# SCH_SOURCE.net
KiCad netlist of a schematic drawn in Altium Designer
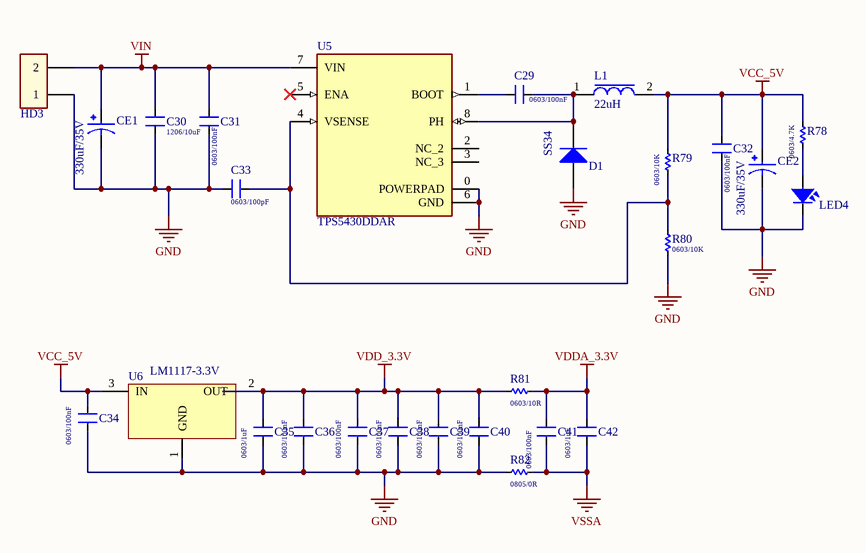
[diagram p0: SCH_SOURCE.SchDoc]

(export (version "E")
  (design (tool "Eeschema 10.0.6"))
  (components
    (comp (ref "C29")
      (value "0603/100nF")
      (footprint "CAP-SMD-0603")
      (libsource (lib "RAL") (part "CAP-SMD"))
    )
    (comp (ref "C30") (value "1206/10uF") (footprint "CAP-SMD-1206") (libsource (lib "RAL") (part "CAP-SMD")))
    (comp (ref "C31")
      (value "0603/100nF")
      (footprint "CAP-SMD-0603")
      (libsource (lib "RAL") (part "CAP-SMD"))
    )
    (comp (ref "C32")
      (value "0603/100nF")
      (footprint "CAP-SMD-0603")
      (libsource (lib "RAL") (part "CAP-SMD"))
    )
    (comp (ref "C33")
      (value "0603/100pF")
      (footprint "CAP-SMD-0603")
      (libsource (lib "RAL") (part "CAP-SMD"))
    )
    (comp (ref "C34")
      (value "0603/100nF")
      (footprint "CAP-SMD-0603")
      (libsource (lib "RAL") (part "CAP-SMD"))
    )
    (comp (ref "C35") (value "0603/1uF") (footprint "CAP-SMD-0603") (libsource (lib "RAL") (part "CAP-SMD")))
    (comp (ref "C36")
      (value "0603/100nF")
      (footprint "CAP-SMD-0603")
      (libsource (lib "RAL") (part "CAP-SMD"))
    )
    (comp (ref "C37")
      (value "0603/100nF")
      (footprint "CAP-SMD-0603")
      (libsource (lib "RAL") (part "CAP-SMD"))
    )
    (comp (ref "C38")
      (value "0603/100nF")
      (footprint "CAP-SMD-0603")
      (libsource (lib "RAL") (part "CAP-SMD"))
    )
    (comp (ref "C39")
      (value "0603/100nF")
      (footprint "CAP-SMD-0603")
      (libsource (lib "RAL") (part "CAP-SMD"))
    )
    (comp (ref "C40")
      (value "0603/100nF")
      (footprint "CAP-SMD-0603")
      (libsource (lib "RAL") (part "CAP-SMD"))
    )
    (comp (ref "C41")
      (value "0603/100nF")
      (footprint "CAP-SMD-0603")
      (libsource (lib "RAL") (part "CAP-SMD"))
    )
    (comp (ref "C42") (value "0603/1uF") (footprint "CAP-SMD-0603") (libsource (lib "RAL") (part "CAP-SMD")))
    (comp (ref "CE1")
      (value "330uF/35V")
      (footprint "CAP-DIP-8x16mm")
      (description "00077126")
      (fields (field (name "PUBLISHER") "Altium Limited"))
      (libsource (lib "mySche") (part "CAP-ALU-DIP"))
    )
    (comp (ref "CE2")
      (value "330uF/35V")
      (footprint "CAP-DIP-8x16mm")
      (description "00077126")
      (fields (field (name "PUBLISHER") "Altium Limited"))
      (libsource (lib "mySche") (part "CAP-ALU-DIP"))
    )
    (comp (ref "D1")
      (value "SS34")
      (footprint "SMB")
      (description "Default Diode")
      (fields (field (name "PUBLISHER") "Altium Limited"))
      (libsource (lib "RAL") (part "Diode SMD"))
    )
    (comp (ref "HD3") (value "Header2") (footprint "XH2.54M-2") (libsource (lib "lib") (part "Header2")))
    (comp (ref "L1")
      (value "22uH")
      (footprint "L-SMD-M-7.3x4.5")
      (fields
        (field (name "PARTNO") "78477010")
        (field (name "MANUFACTURER") "Wurth Elektronik")
        (field (name "CREATED BY") "Baojun Chen")
      )
      (libsource (lib "RAL") (part "L-SMD-1"))
    )
    (comp (ref "LED4") (value "LED") (footprint "LED-0805-Green") (libsource (lib "RAL") (part "LED1-SMD")))
    (comp (ref "R78")
      (value "0603/4.7K")
      (footprint "RES-SMD-0603")
      (description "Resistor")
      (fields
        (field (name "MANUFACTURER") "Generic Components")
        (field (name "PUBLISHER") "Altium Hobart Technology Centre")
      )
      (libsource (lib "RAL") (part "Res-SMD"))
    )
    (comp (ref "R79")
      (value "0603/10K")
      (footprint "RES-SMD-0603")
      (description "Resistor")
      (fields
        (field (name "MANUFACTURER") "Generic Components")
        (field (name "PUBLISHER") "Altium Hobart Technology Centre")
      )
      (libsource (lib "RAL") (part "Res-SMD"))
    )
    (comp (ref "R80")
      (value "0603/10K")
      (footprint "RES-SMD-0603")
      (description "Resistor")
      (fields
        (field (name "MANUFACTURER") "Generic Components")
        (field (name "PUBLISHER") "Altium Hobart Technology Centre")
      )
      (libsource (lib "RAL") (part "Res-SMD"))
    )
    (comp (ref "R81")
      (value "0603/10R")
      (footprint "RES-SMD-0603")
      (description "Resistor")
      (fields
        (field (name "MANUFACTURER") "Generic Components")
        (field (name "PUBLISHER") "Altium Hobart Technology Centre")
      )
      (libsource (lib "RAL") (part "Res-SMD"))
    )
    (comp (ref "R82")
      (value "0805/0R")
      (footprint "RES-SMD-0805")
      (description "Resistor")
      (fields
        (field (name "MANUFACTURER") "Generic Components")
        (field (name "PUBLISHER") "Altium Hobart Technology Centre")
      )
      (libsource (lib "RAL") (part "Res-SMD"))
    )
    (comp (ref "U5")
      (value "TPS5430DDAR")
      (footprint "SOP-8 + GND")
      (description "5.5V to 36V Input, 3A, 500kHz Step-Down Converter")
      (fields (field (name "MF") "Texas Instruments"))
      (libsource (lib "lib") (part "TPS5430DDAR"))
    )
    (comp (ref "U6")
      (value "LM1117-3.3V")
      (footprint "TO252-123")
      (description "800mA Low-Dropout Linear Regulator")
      (fields (field (name "CREATOR") "Nguyen Ba Bien"))
      (libsource (lib "RAL") (part "IC LM1117"))
    )
  )
  (nets
    (net (code "1") (name "GND") (class "Default")
      (node (ref "C30") (pin "2") (pinfunction "2_2") (pintype "passive"))
      (node (ref "C31") (pin "2") (pinfunction "2_2") (pintype "passive"))
      (node (ref "C32") (pin "2") (pinfunction "2_2") (pintype "passive"))
      (node (ref "C33") (pin "1") (pinfunction "1_1") (pintype "passive"))
      (node (ref "C34") (pin "1") (pinfunction "1_1") (pintype "passive"))
      (node (ref "C35") (pin "1") (pinfunction "1_1") (pintype "passive"))
      (node (ref "C36") (pin "1") (pinfunction "1_1") (pintype "passive"))
      (node (ref "C37") (pin "1") (pinfunction "1_1") (pintype "passive"))
      (node (ref "C38") (pin "1") (pinfunction "1_1") (pintype "passive"))
      (node (ref "C39") (pin "1") (pinfunction "1_1") (pintype "passive"))
      (node (ref "C40") (pin "1") (pinfunction "1_1") (pintype "passive"))
      (node (ref "CE1") (pin "2") (pinfunction "2_2") (pintype "passive"))
      (node (ref "CE2") (pin "2") (pinfunction "2_2") (pintype "passive"))
      (node (ref "D1") (pin "1") (pinfunction "A_1") (pintype "passive"))
      (node (ref "HD3") (pin "1") (pinfunction "1_1") (pintype "passive"))
      (node (ref "LED4") (pin "2") (pinfunction "2_2") (pintype "passive"))
      (node (ref "R80") (pin "1") (pinfunction "1_1") (pintype "passive"))
      (node (ref "R82") (pin "1") (pinfunction "1_1") (pintype "passive"))
      (node (ref "U5") (pin "0") (pinfunction "POWERPAD_0") (pintype "power_in"))
      (node (ref "U5") (pin "6") (pinfunction "GND_6") (pintype "power_in"))
      (node (ref "U6") (pin "1") (pinfunction "GND_1") (pintype "passive"))
    )
    (net (code "2") (name "Net-(D1-K)") (class "Default")
      (node (ref "C29") (pin "1") (pinfunction "1_1") (pintype "passive"))
      (node (ref "D1") (pin "2") (pinfunction "K_2") (pintype "passive"))
      (node (ref "L1") (pin "1") (pinfunction "1_1") (pintype "passive"))
      (node (ref "U5") (pin "8") (pinfunction "PH_8") (pintype "bidirectional"))
    )
    (net (code "3") (name "Net-(LED4-Pad1)") (class "Default")
      (node (ref "LED4") (pin "1") (pinfunction "1_1") (pintype "passive"))
      (node (ref "R78") (pin "2") (pinfunction "2_2") (pintype "passive"))
    )
    (net (code "4") (name "Net-(U5-BOOT)") (class "Default")
      (node (ref "C29") (pin "2") (pinfunction "2_2") (pintype "passive"))
      (node (ref "U5") (pin "1") (pinfunction "BOOT_1") (pintype "output"))
    )
    (net (code "5") (name "Net-(U5-VSENSE)") (class "Default")
      (node (ref "C33") (pin "2") (pinfunction "2_2") (pintype "passive"))
      (node (ref "R79") (pin "2") (pinfunction "2_2") (pintype "passive"))
      (node (ref "R80") (pin "2") (pinfunction "2_2") (pintype "passive"))
      (node (ref "U5") (pin "4") (pinfunction "VSENSE_4") (pintype "input"))
    )
    (net (code "6") (name "VCC_5V") (class "Default")
      (node (ref "C32") (pin "1") (pinfunction "1_1") (pintype "passive"))
      (node (ref "C34") (pin "2") (pinfunction "2_2") (pintype "passive"))
      (node (ref "CE2") (pin "1") (pinfunction "1_1") (pintype "passive"))
      (node (ref "L1") (pin "2") (pinfunction "2_2") (pintype "passive"))
      (node (ref "R78") (pin "1") (pinfunction "1_1") (pintype "passive"))
      (node (ref "R79") (pin "1") (pinfunction "1_1") (pintype "passive"))
      (node (ref "U6") (pin "3") (pinfunction "IN_3") (pintype "passive"))
    )
    (net (code "7") (name "VDDA_3.3V") (class "Default")
      (node (ref "C41") (pin "2") (pinfunction "2_2") (pintype "passive"))
      (node (ref "C42") (pin "2") (pinfunction "2_2") (pintype "passive"))
      (node (ref "R81") (pin "2") (pinfunction "2_2") (pintype "passive"))
    )
    (net (code "8") (name "VDD_3.3V") (class "Default")
      (node (ref "C35") (pin "2") (pinfunction "2_2") (pintype "passive"))
      (node (ref "C36") (pin "2") (pinfunction "2_2") (pintype "passive"))
      (node (ref "C37") (pin "2") (pinfunction "2_2") (pintype "passive"))
      (node (ref "C38") (pin "2") (pinfunction "2_2") (pintype "passive"))
      (node (ref "C39") (pin "2") (pinfunction "2_2") (pintype "passive"))
      (node (ref "C40") (pin "2") (pinfunction "2_2") (pintype "passive"))
      (node (ref "R81") (pin "1") (pinfunction "1_1") (pintype "passive"))
      (node (ref "U6") (pin "2") (pinfunction "OUT_2") (pintype "passive"))
    )
    (net (code "9") (name "VIN") (class "Default")
      (node (ref "C30") (pin "1") (pinfunction "1_1") (pintype "passive"))
      (node (ref "C31") (pin "1") (pinfunction "1_1") (pintype "passive"))
      (node (ref "CE1") (pin "1") (pinfunction "1_1") (pintype "passive"))
      (node (ref "HD3") (pin "2") (pinfunction "2_2") (pintype "passive"))
      (node (ref "U5") (pin "7") (pinfunction "VIN_7") (pintype "power_in"))
    )
    (net (code "10") (name "VSSA") (class "Default")
      (node (ref "C41") (pin "1") (pinfunction "1_1") (pintype "passive"))
      (node (ref "C42") (pin "1") (pinfunction "1_1") (pintype "passive"))
      (node (ref "R82") (pin "2") (pinfunction "2_2") (pintype "passive"))
    )
    (net (code "11") (name "unconnected-(U5-ENA-Pad5)") (class "Default")
      (node (ref "U5") (pin "5") (pinfunction "ENA_5") (pintype "input+no_connect"))
    )
    (net (code "12") (name "unconnected-(U5-NC_2-Pad2)") (class "Default")
      (node (ref "U5") (pin "2") (pinfunction "NC_2_2") (pintype "passive"))
    )
    (net (code "13") (name "unconnected-(U5-NC_3-Pad3)") (class "Default")
      (node (ref "U5") (pin "3") (pinfunction "NC_3_3") (pintype "passive"))
    )
  )
)
